# nav.net
KiCad netlist of a schematic drawn in EAGLE
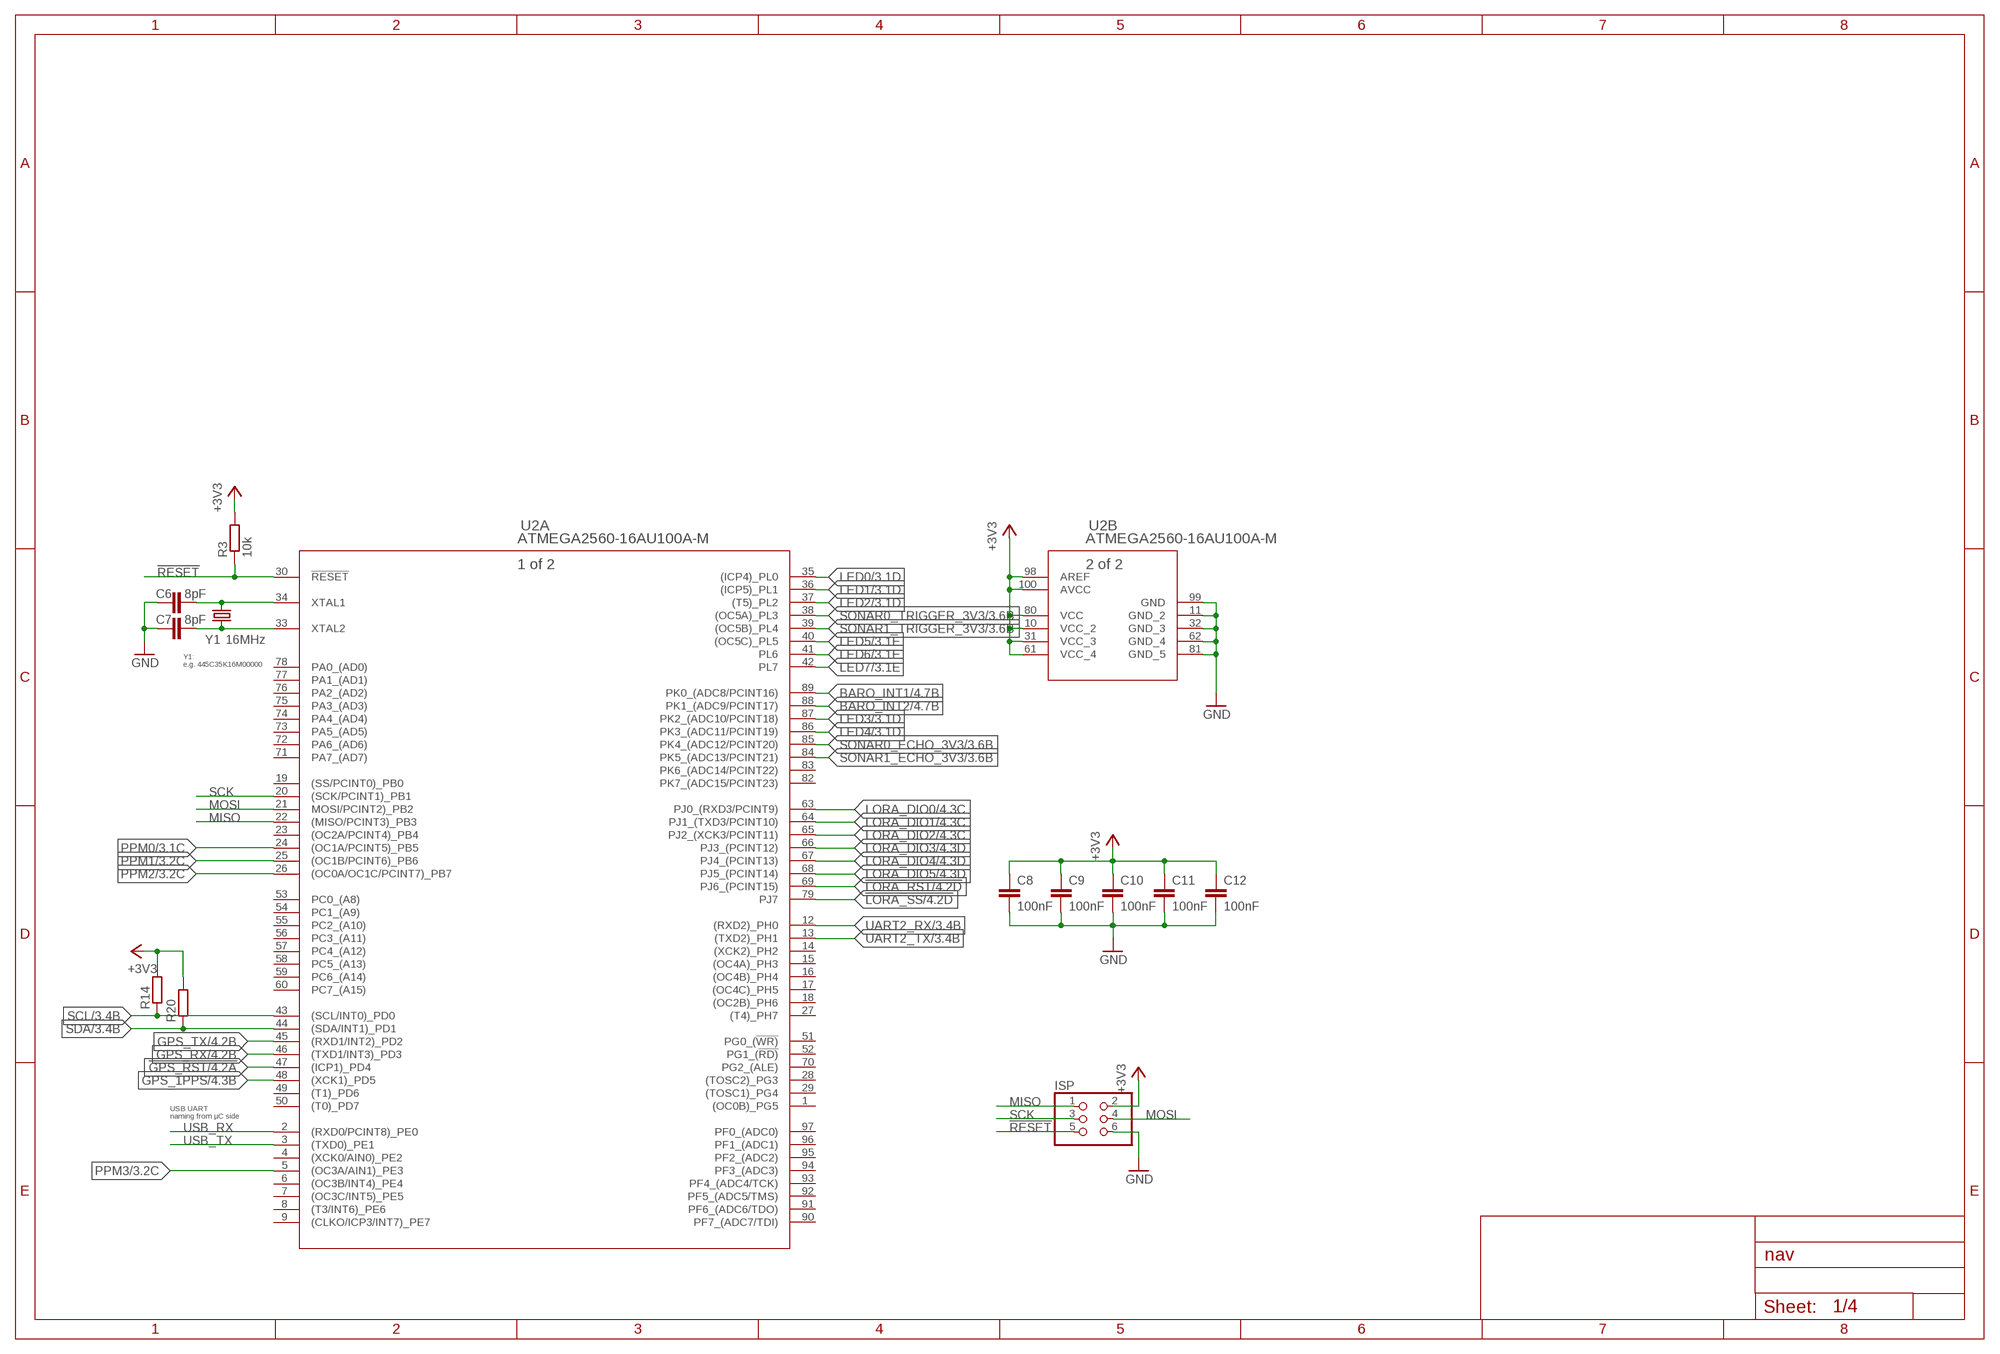
[diagram p0: schematic, sheet 1]
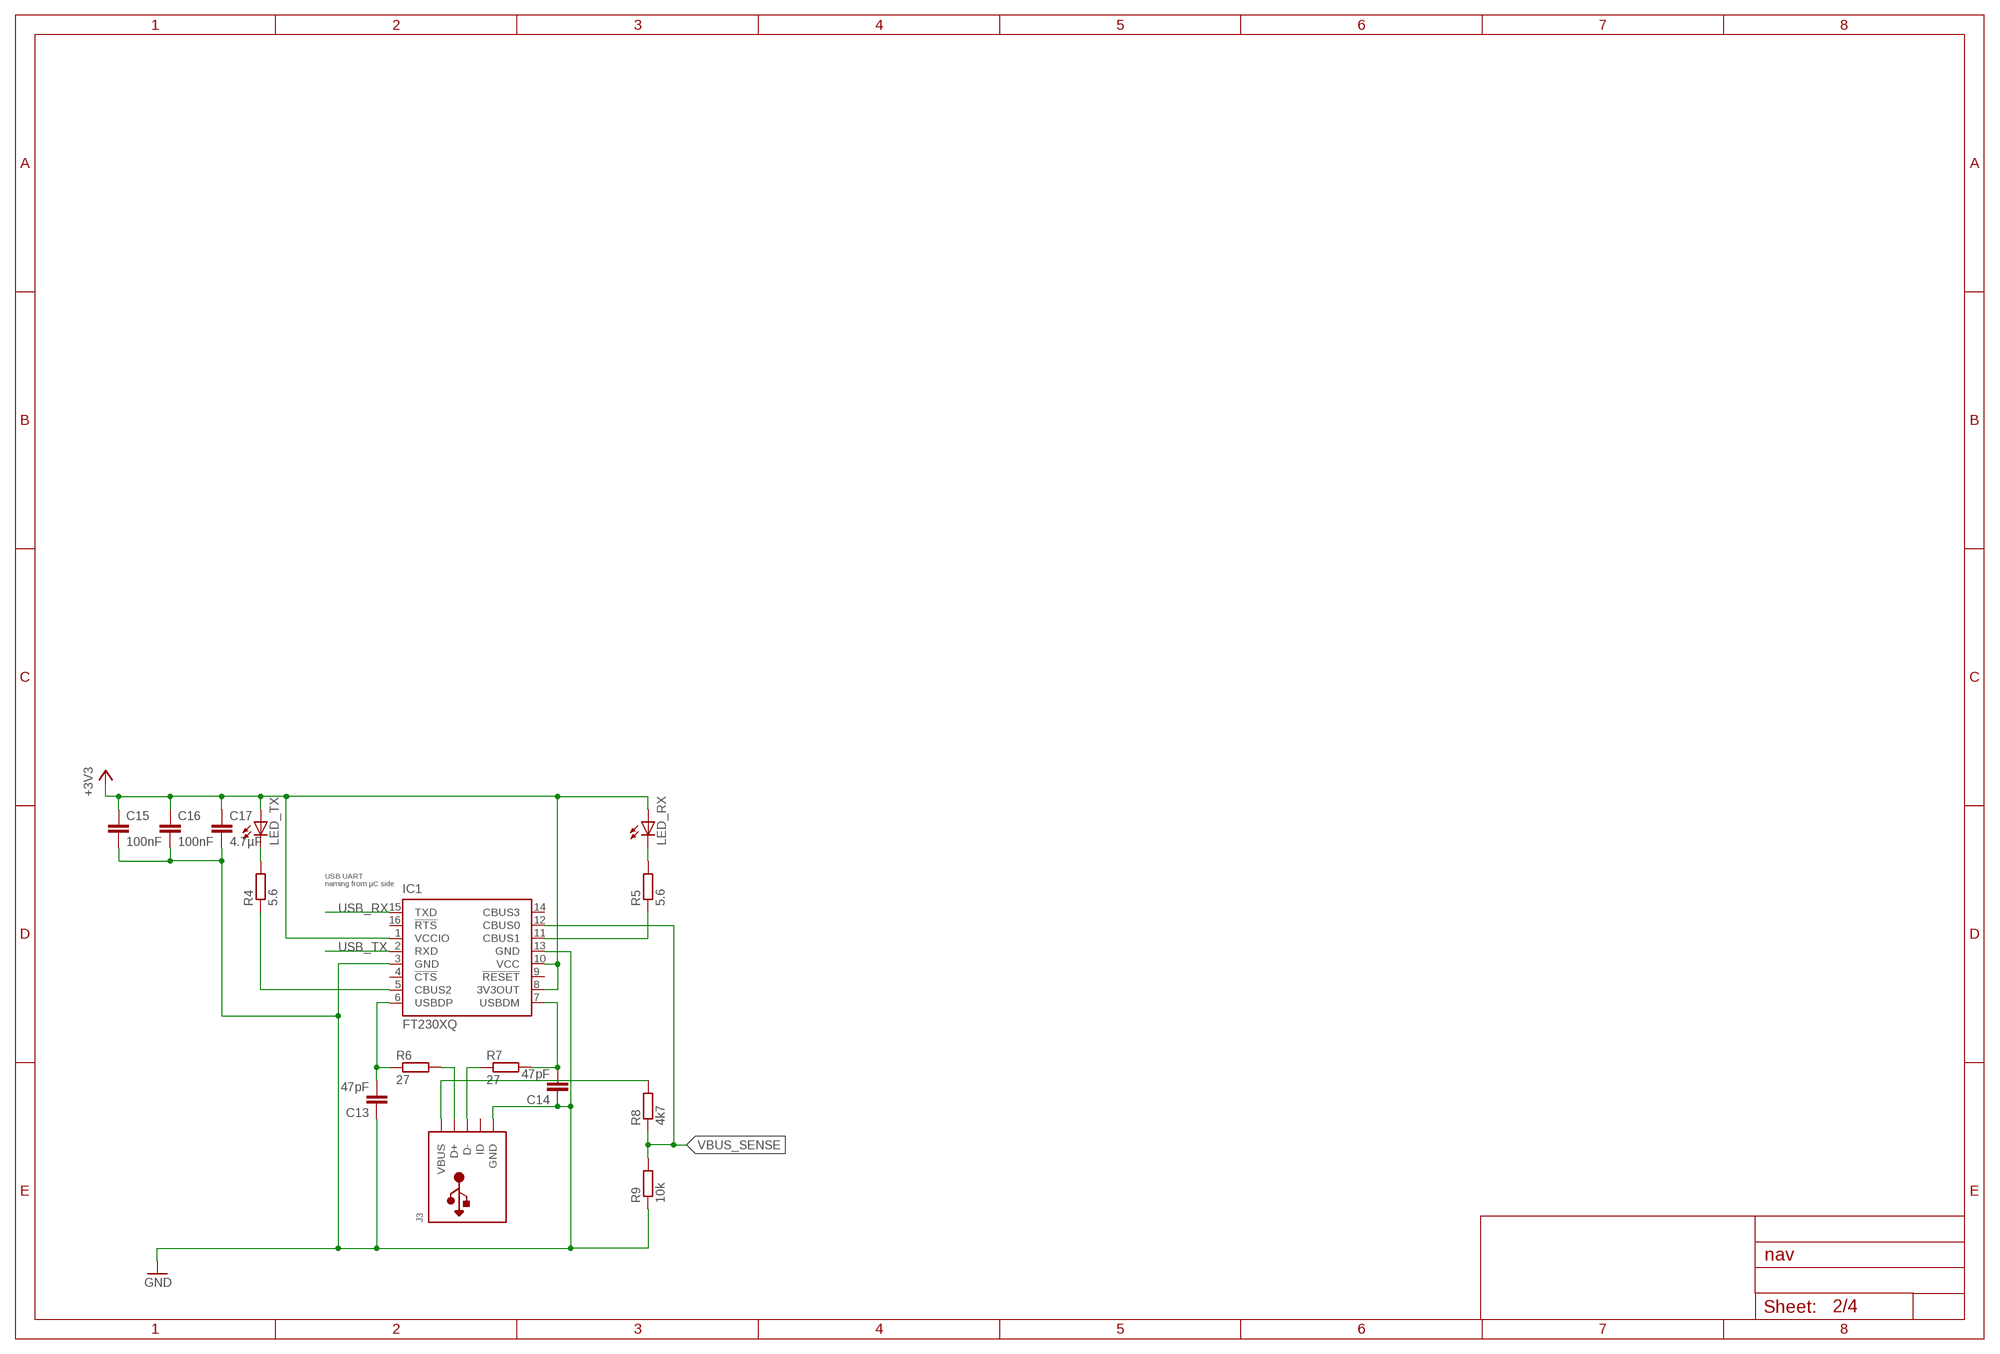
[diagram p1: schematic, sheet 2]
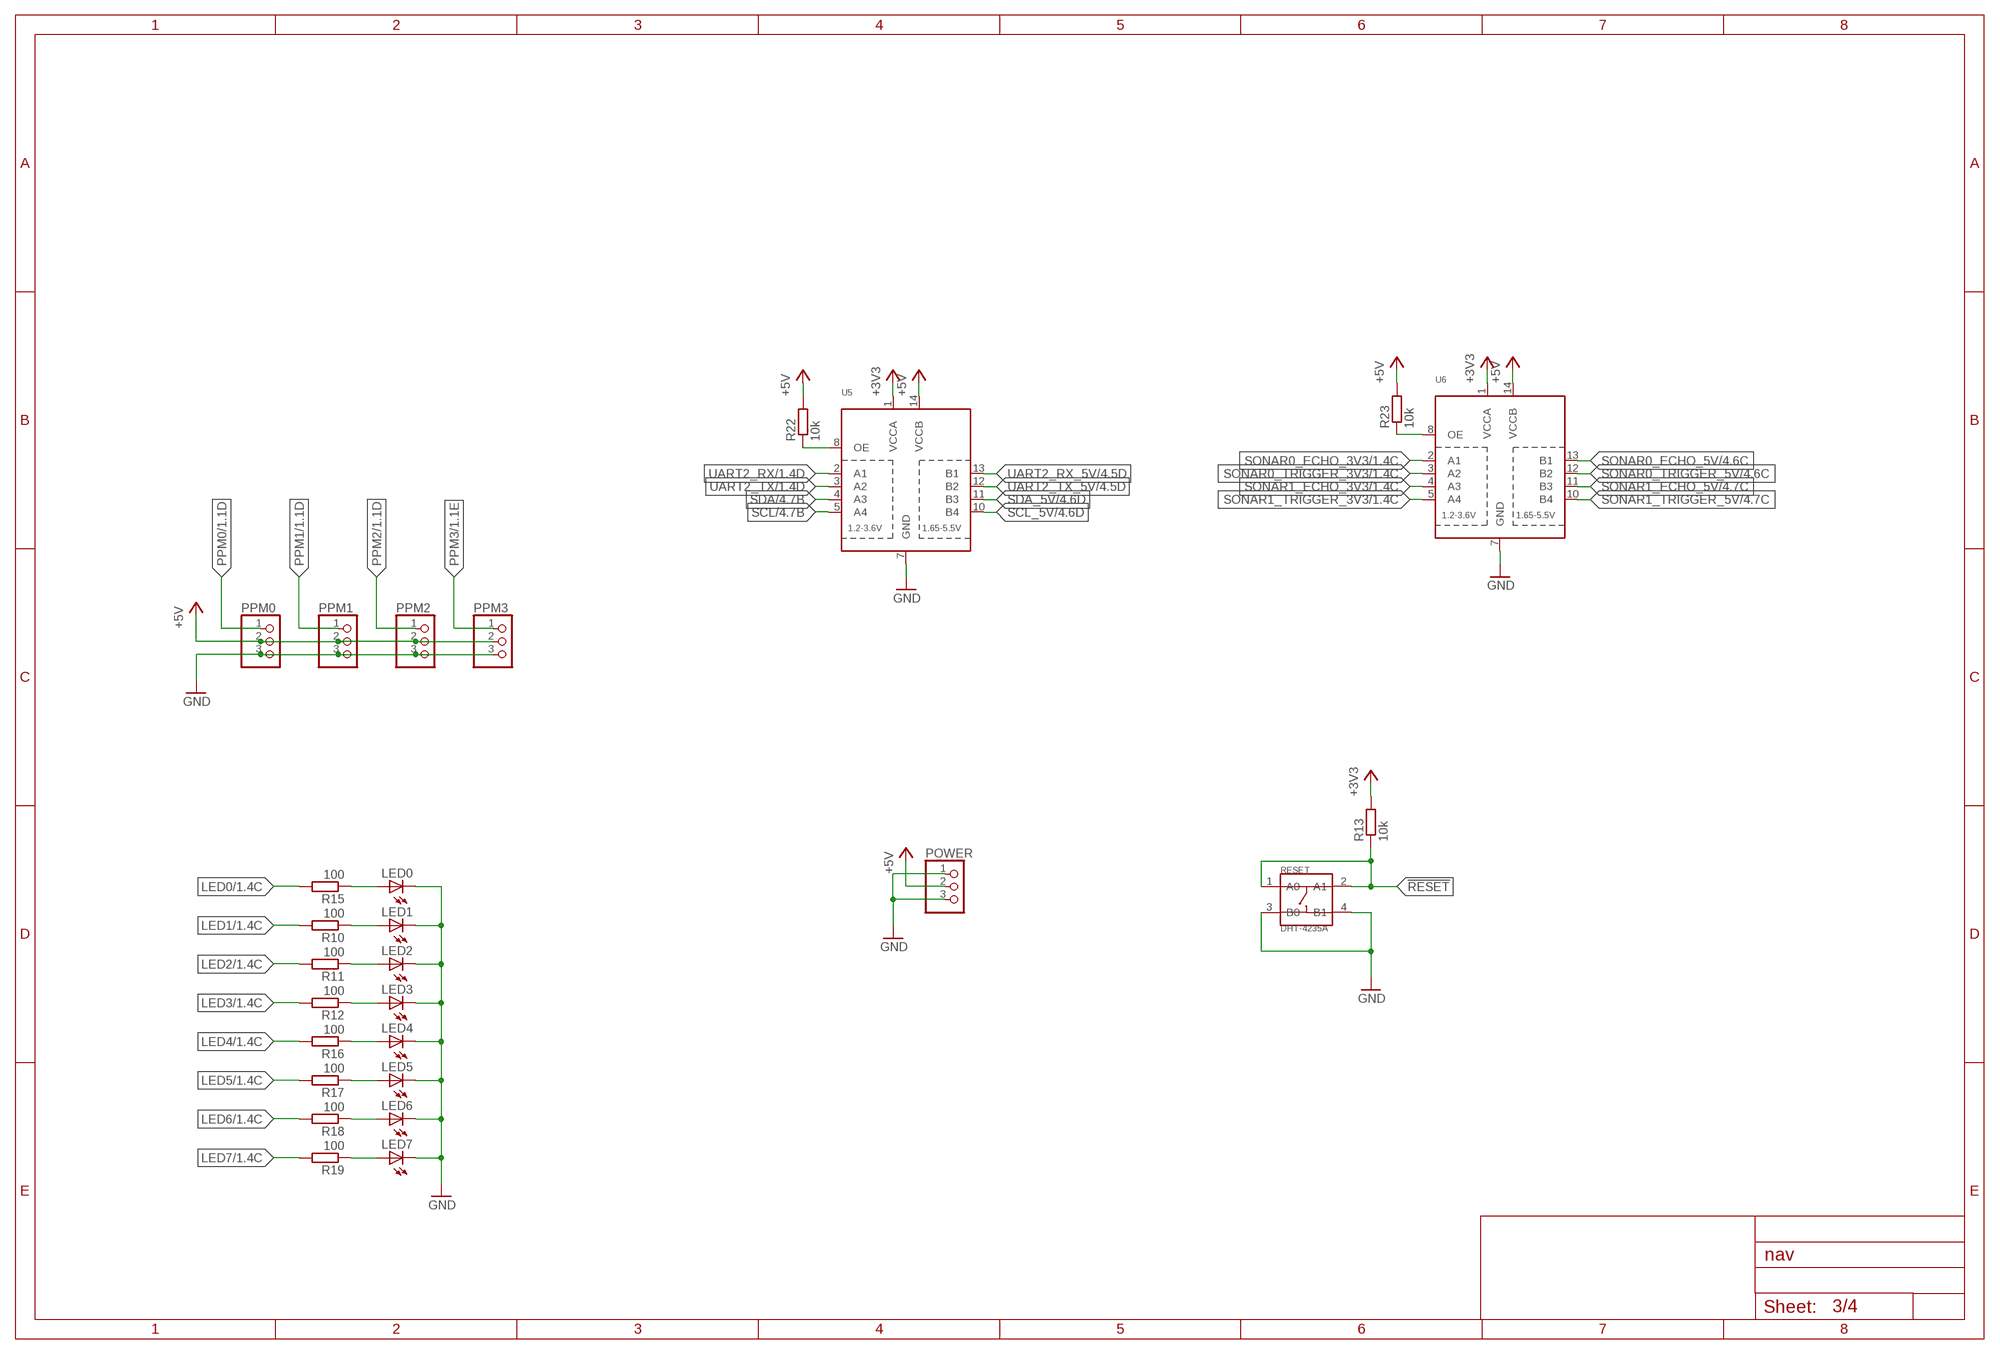
[diagram p2: schematic, sheet 3]
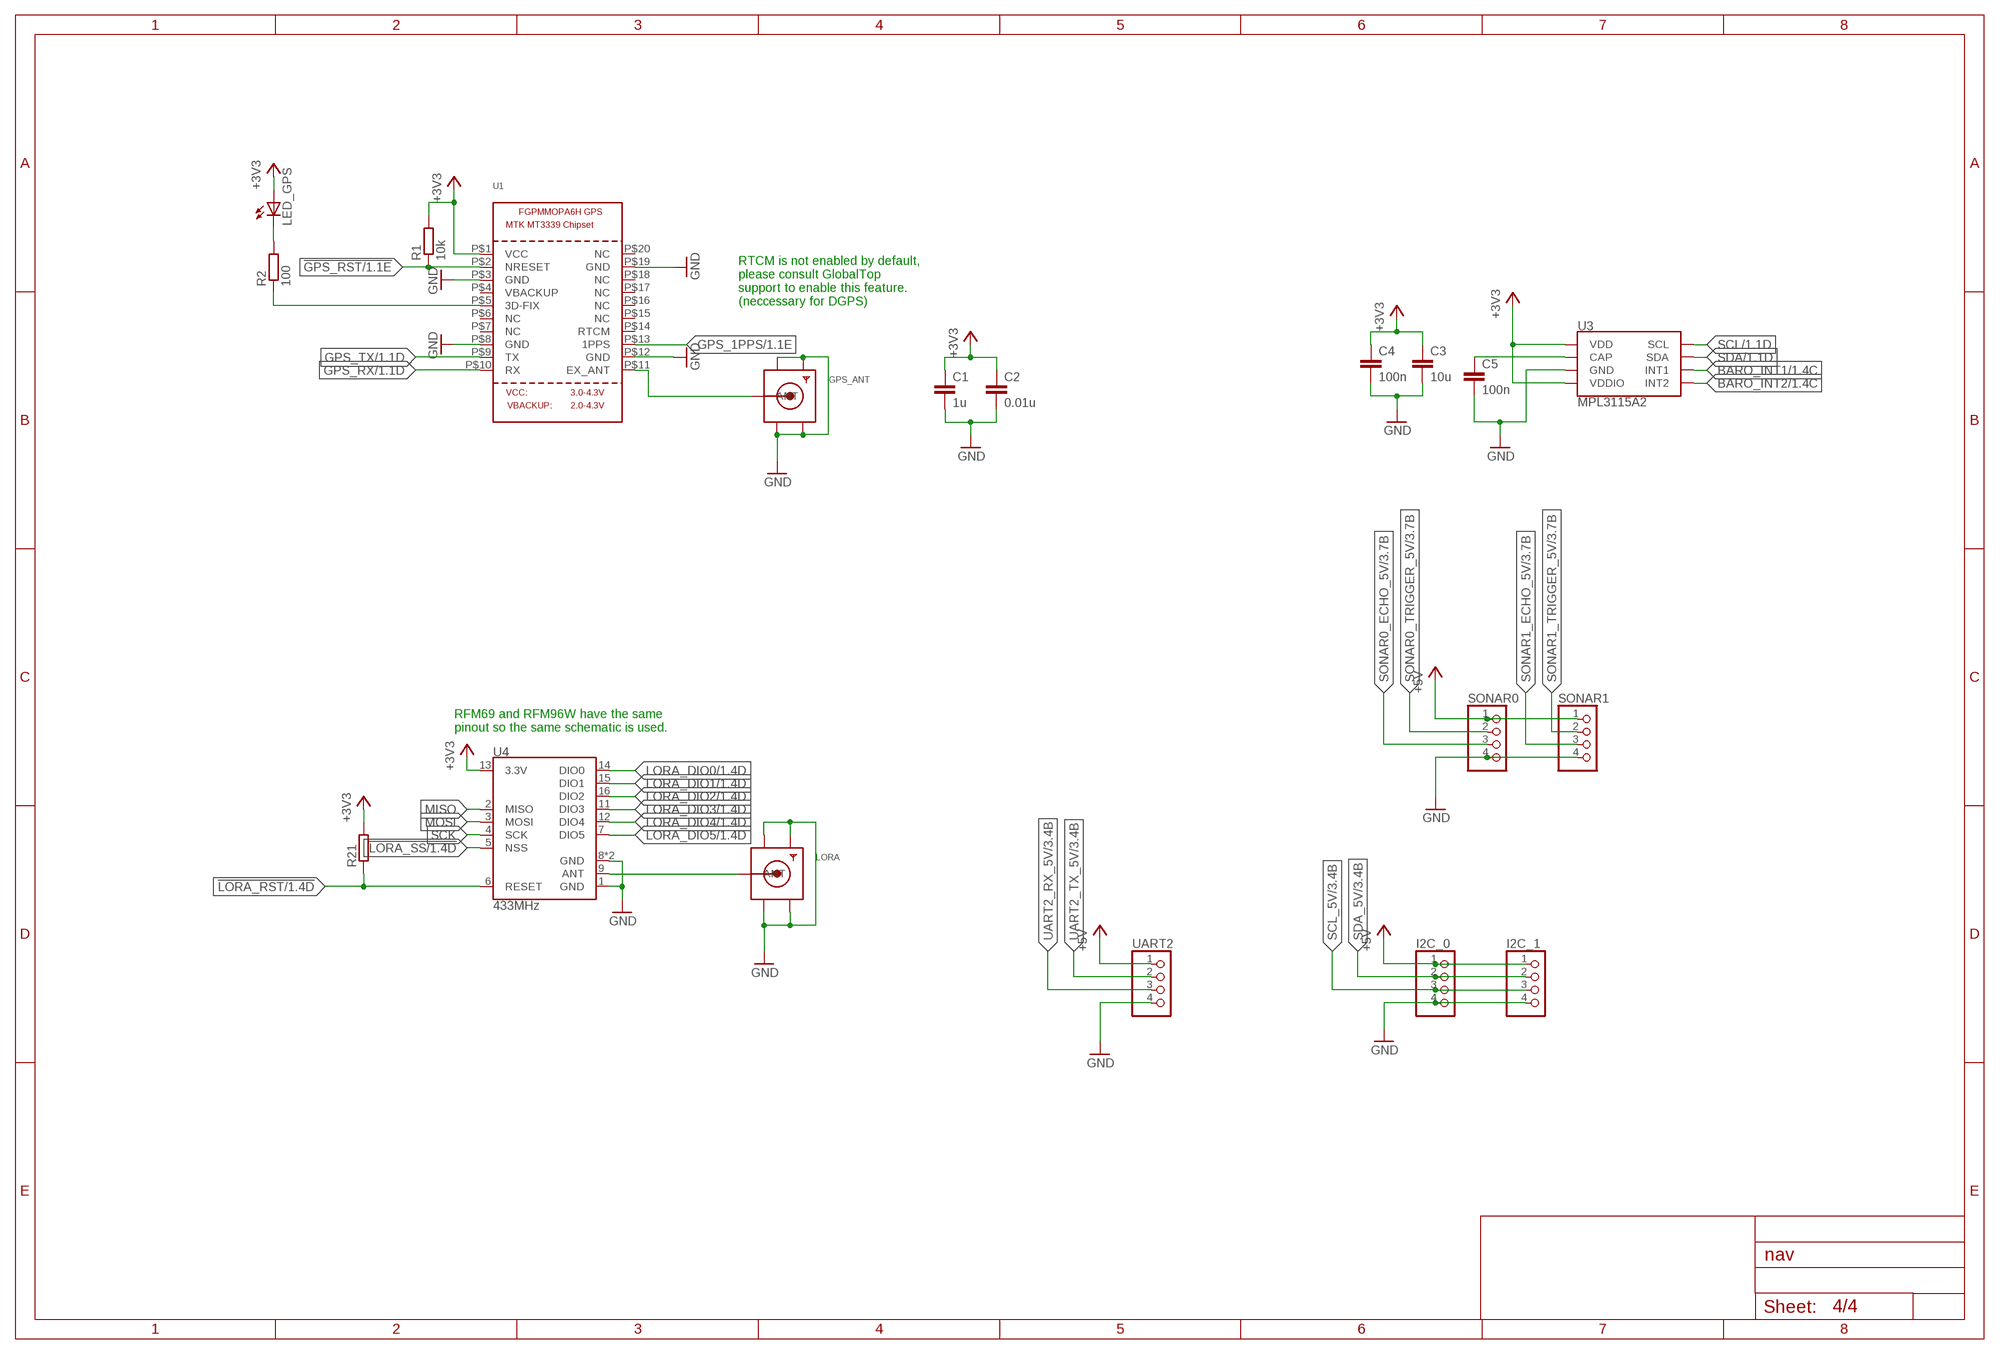
[diagram p3: schematic, sheet 4]

(export (version "E")
  (design (tool "Eeschema 10.0.6"))
  (components
    (comp (ref "LED0")
      (value "LEDCHIP-LED0603")
      (footprint "eagle-import:CHIP-LED0603")
      (libsource (lib "eagle-import") (part "LEDCHIP-LED0603"))
    )
    (comp (ref "LED1")
      (value "LEDCHIP-LED0603")
      (footprint "eagle-import:CHIP-LED0603")
      (libsource (lib "eagle-import") (part "LEDCHIP-LED0603"))
    )
    (comp (ref "LED2")
      (value "LEDCHIP-LED0603")
      (footprint "eagle-import:CHIP-LED0603")
      (libsource (lib "eagle-import") (part "LEDCHIP-LED0603"))
    )
    (comp (ref "LED3")
      (value "LEDCHIP-LED0603")
      (footprint "eagle-import:CHIP-LED0603")
      (libsource (lib "eagle-import") (part "LEDCHIP-LED0603"))
    )
    (comp (ref "LED4")
      (value "LEDCHIP-LED0603")
      (footprint "eagle-import:CHIP-LED0603")
      (libsource (lib "eagle-import") (part "LEDCHIP-LED0603"))
    )
    (comp (ref "LED5")
      (value "LEDCHIP-LED0603")
      (footprint "eagle-import:CHIP-LED0603")
      (libsource (lib "eagle-import") (part "LEDCHIP-LED0603"))
    )
    (comp (ref "LED6")
      (value "LEDCHIP-LED0603")
      (footprint "eagle-import:CHIP-LED0603")
      (libsource (lib "eagle-import") (part "LEDCHIP-LED0603"))
    )
    (comp (ref "LED7")
      (value "LEDCHIP-LED0603")
      (footprint "eagle-import:CHIP-LED0603")
      (libsource (lib "eagle-import") (part "LEDCHIP-LED0603"))
    )
    (comp (ref "POWER")
      (value "PINHD-1X3")
      (footprint "eagle-import:1X03")
      (libsource (lib "eagle-import") (part "PINHD-1X3"))
    )
    (comp (ref "PPM0")
      (value "PINHD-1X3")
      (footprint "eagle-import:1X03")
      (libsource (lib "eagle-import") (part "PINHD-1X3"))
    )
    (comp (ref "PPM1")
      (value "PINHD-1X3")
      (footprint "eagle-import:1X03")
      (libsource (lib "eagle-import") (part "PINHD-1X3"))
    )
    (comp (ref "PPM2")
      (value "PINHD-1X3")
      (footprint "eagle-import:1X03")
      (libsource (lib "eagle-import") (part "PINHD-1X3"))
    )
    (comp (ref "PPM3")
      (value "PINHD-1X3")
      (footprint "eagle-import:1X03")
      (libsource (lib "eagle-import") (part "PINHD-1X3"))
    )
    (comp (ref "R10")
      (value "100")
      (footprint "eagle-import:R0603")
      (libsource (lib "eagle-import") (part "R-EU_R0603"))
    )
    (comp (ref "R11")
      (value "100")
      (footprint "eagle-import:R0603")
      (libsource (lib "eagle-import") (part "R-EU_R0603"))
    )
    (comp (ref "R12")
      (value "100")
      (footprint "eagle-import:R0603")
      (libsource (lib "eagle-import") (part "R-EU_R0603"))
    )
    (comp (ref "R13")
      (value "10k")
      (footprint "eagle-import:R0603")
      (libsource (lib "eagle-import") (part "resistor_348_R-EU_R0603"))
    )
    (comp (ref "R15")
      (value "100")
      (footprint "eagle-import:R0603")
      (libsource (lib "eagle-import") (part "R-EU_R0603"))
    )
    (comp (ref "R16")
      (value "100")
      (footprint "eagle-import:R0603")
      (libsource (lib "eagle-import") (part "R-EU_R0603"))
    )
    (comp (ref "R17")
      (value "100")
      (footprint "eagle-import:R0603")
      (libsource (lib "eagle-import") (part "R-EU_R0603"))
    )
    (comp (ref "R18")
      (value "100")
      (footprint "eagle-import:R0603")
      (libsource (lib "eagle-import") (part "R-EU_R0603"))
    )
    (comp (ref "R19")
      (value "100")
      (footprint "eagle-import:R0603")
      (libsource (lib "eagle-import") (part "R-EU_R0603"))
    )
    (comp (ref "R22")
      (value "10k")
      (footprint "eagle-import:R0603")
      (libsource (lib "eagle-import") (part "resistor_348_R-EU_R0603"))
    )
    (comp (ref "R23")
      (value "10k")
      (footprint "eagle-import:R0603")
      (libsource (lib "eagle-import") (part "resistor_348_R-EU_R0603"))
    )
    (comp (ref "RESET")
      (value "DHT-4235A")
      (footprint "eagle-import:SW4-SMD-4.2X3.2X2.5MM")
      (libsource (lib "eagle-import") (part "SMD-BUTTON-TOP-DHT-4235A(4P-4.2X3.2MM)"))
    )
    (comp (ref "U5")
      (value "TXB0104PWR")
      (footprint "eagle-import:TSSOP14")
      (libsource (lib "eagle-import") (part "TXB0104PWR"))
    )
    (comp (ref "U6")
      (value "TXB0104PWR")
      (footprint "eagle-import:TSSOP14")
      (libsource (lib "eagle-import") (part "TXB0104PWR"))
    )
    (comp (ref "C6")
      (value "8pF")
      (footprint "eagle-import:C0603")
      (libsource (lib "eagle-import") (part "C-EUC0603"))
    )
    (comp (ref "C7")
      (value "8pF")
      (footprint "eagle-import:C0603")
      (libsource (lib "eagle-import") (part "C-EUC0603"))
    )
    (comp (ref "C8")
      (value "100nF")
      (footprint "eagle-import:C0603")
      (libsource (lib "eagle-import") (part "C-EUC0603"))
    )
    (comp (ref "C9")
      (value "100nF")
      (footprint "eagle-import:C0603")
      (libsource (lib "eagle-import") (part "C-EUC0603"))
    )
    (comp (ref "C10")
      (value "100nF")
      (footprint "eagle-import:C0603")
      (libsource (lib "eagle-import") (part "C-EUC0603"))
    )
    (comp (ref "C11")
      (value "100nF")
      (footprint "eagle-import:C0603")
      (libsource (lib "eagle-import") (part "C-EUC0603"))
    )
    (comp (ref "C12")
      (value "100nF")
      (footprint "eagle-import:C0603")
      (libsource (lib "eagle-import") (part "C-EUC0603"))
    )
    (comp (ref "ISP")
      (value "PINHD-2X3")
      (footprint "eagle-import:2X03")
      (libsource (lib "eagle-import") (part "PINHD-2X3"))
    )
    (comp (ref "R3")
      (value "10k")
      (footprint "eagle-import:R0603")
      (libsource (lib "eagle-import") (part "R-EU_R0603"))
    )
    (comp (ref "R14")
      (value "R-EU_R0603")
      (footprint "eagle-import:R0603")
      (libsource (lib "eagle-import") (part "resistor_348_R-EU_R0603"))
    )
    (comp (ref "R20")
      (value "R-EU_R0603")
      (footprint "eagle-import:R0603")
      (libsource (lib "eagle-import") (part "resistor_348_R-EU_R0603"))
    )
    (comp (ref "U2")
      (value "ATMEGA2560-16AU100A-M")
      (footprint "eagle-import:100A-M")
      (fields (field (name "MANUFACTURER_PART_NUMBER") "ATMEGA256016AU"))
      (libsource (lib "eagle-import") (part "ATMEGA2560-16AU100A-M"))
    )
    (comp (ref "Y1")
      (value "16MHz")
      (footprint "eagle-import:CRYSTAL-SMD-5X3.2-2PAD")
      (libsource (lib "eagle-import") (part "CRYSTALSMD-5X3.2-2PAD"))
    )
    (comp (ref "C13")
      (value "47pF")
      (footprint "eagle-import:C0603")
      (libsource (lib "eagle-import") (part "C-EUC0603"))
    )
    (comp (ref "C14")
      (value "47pF")
      (footprint "eagle-import:C0603")
      (libsource (lib "eagle-import") (part "C-EUC0603"))
    )
    (comp (ref "C15")
      (value "100nF")
      (footprint "eagle-import:C0603")
      (libsource (lib "eagle-import") (part "C-EUC0603"))
    )
    (comp (ref "C16")
      (value "100nF")
      (footprint "eagle-import:C0603")
      (libsource (lib "eagle-import") (part "C-EUC0603"))
    )
    (comp (ref "C17")
      (value "4.7µF")
      (footprint "eagle-import:C0603")
      (libsource (lib "eagle-import") (part "C-EUC0603"))
    )
    (comp (ref "IC1")
      (value "FT230XQ")
      (footprint "eagle-import:QFN16")
      (libsource (lib "eagle-import") (part "FT230XQ"))
    )
    (comp (ref "J3")
      (value "USBMINIB")
      (footprint "eagle-import:USB-MINIB")
      (libsource (lib "eagle-import") (part "USBMINIB"))
    )
    (comp (ref "LED_RX")
      (value "LEDCHIP-LED0603")
      (footprint "eagle-import:CHIP-LED0603")
      (libsource (lib "eagle-import") (part "LEDCHIP-LED0603"))
    )
    (comp (ref "LED_TX")
      (value "LEDCHIP-LED0603")
      (footprint "eagle-import:CHIP-LED0603")
      (libsource (lib "eagle-import") (part "LEDCHIP-LED0603"))
    )
    (comp (ref "R4")
      (value "5.6")
      (footprint "eagle-import:R0603")
      (libsource (lib "eagle-import") (part "R-EU_R0603"))
    )
    (comp (ref "R5")
      (value "5.6")
      (footprint "eagle-import:R0603")
      (libsource (lib "eagle-import") (part "R-EU_R0603"))
    )
    (comp (ref "R6")
      (value "27")
      (footprint "eagle-import:R0603")
      (libsource (lib "eagle-import") (part "R-EU_R0603"))
    )
    (comp (ref "R7")
      (value "27")
      (footprint "eagle-import:R0603")
      (libsource (lib "eagle-import") (part "R-EU_R0603"))
    )
    (comp (ref "R8")
      (value "4k7")
      (footprint "eagle-import:R0603")
      (libsource (lib "eagle-import") (part "R-EU_R0603"))
    )
    (comp (ref "R9")
      (value "10k")
      (footprint "eagle-import:R0603")
      (libsource (lib "eagle-import") (part "R-EU_R0603"))
    )
    (comp (ref "C1")
      (value "1u")
      (footprint "eagle-import:C0603")
      (libsource (lib "eagle-import") (part "resistor_348_C-EUC0603"))
    )
    (comp (ref "C2")
      (value "0.01u")
      (footprint "eagle-import:C0603")
      (libsource (lib "eagle-import") (part "resistor_348_C-EUC0603"))
    )
    (comp (ref "C3")
      (value "10u")
      (footprint "eagle-import:C0603")
      (libsource (lib "eagle-import") (part "resistor_348_C-EUC0603"))
    )
    (comp (ref "C4")
      (value "100n")
      (footprint "eagle-import:C0603")
      (libsource (lib "eagle-import") (part "resistor_348_C-EUC0603"))
    )
    (comp (ref "C5")
      (value "100n")
      (footprint "eagle-import:C0603")
      (libsource (lib "eagle-import") (part "resistor_348_C-EUC0603"))
    )
    (comp (ref "GPS_ANT")
      (value "SMACONNECTOR_EDGE")
      (footprint "eagle-import:SMA_EDGELAUNCH")
      (libsource (lib "eagle-import") (part "SMACONNECTOR_EDGE"))
    )
    (comp (ref "I2C_0")
      (value "PINHD-1X4")
      (footprint "eagle-import:1X04")
      (libsource (lib "eagle-import") (part "PINHD-1X4"))
    )
    (comp (ref "I2C_1")
      (value "PINHD-1X4")
      (footprint "eagle-import:1X04")
      (libsource (lib "eagle-import") (part "PINHD-1X4"))
    )
    (comp (ref "LED_GPS")
      (value "LEDCHIP-LED0603")
      (footprint "eagle-import:CHIP-LED0603")
      (libsource (lib "eagle-import") (part "LEDCHIP-LED0603"))
    )
    (comp (ref "LORA")
      (value "SMACONNECTOR_EDGE")
      (footprint "eagle-import:SMA_EDGELAUNCH")
      (libsource (lib "eagle-import") (part "SMACONNECTOR_EDGE"))
    )
    (comp (ref "R1")
      (value "10k")
      (footprint "eagle-import:R0603")
      (libsource (lib "eagle-import") (part "resistor_348_R-EU_R0603"))
    )
    (comp (ref "R2")
      (value "100")
      (footprint "eagle-import:R0603")
      (libsource (lib "eagle-import") (part "resistor_348_R-EU_R0603"))
    )
    (comp (ref "R21")
      (value "R-EU_R0603")
      (footprint "eagle-import:R0603")
      (libsource (lib "eagle-import") (part "resistor_348_R-EU_R0603"))
    )
    (comp (ref "SONAR0")
      (value "PINHD-1X4")
      (footprint "eagle-import:1X04")
      (libsource (lib "eagle-import") (part "PINHD-1X4"))
    )
    (comp (ref "SONAR1")
      (value "PINHD-1X4")
      (footprint "eagle-import:1X04")
      (libsource (lib "eagle-import") (part "PINHD-1X4"))
    )
    (comp (ref "U1")
      (value "GPS_FGPMMOPA6H")
      (footprint "eagle-import:FGPMMOPA6H")
      (libsource (lib "eagle-import") (part "GPS_FGPMMOPA6H"))
    )
    (comp (ref "U3")
      (value "MPL3115A2")
      (footprint "eagle-import:LGA-8-5X3")
      (libsource (lib "eagle-import") (part "MPL3115A2"))
    )
    (comp (ref "U4")
      (value "433MHz")
      (footprint "eagle-import:RFM69HCW-XXXS2")
      (libsource (lib "eagle-import") (part "RFM69HCW-433"))
    )
    (comp (ref "UART2")
      (value "PINHD-1X4")
      (footprint "eagle-import:1X04")
      (libsource (lib "eagle-import") (part "PINHD-1X4"))
    )
  )
  (nets
    (net (code "1") (name "+3V3") (class "Default")
      (node (ref "C1") (pin "1") (pinfunction "1_1") (pintype "passive"))
      (node (ref "C10") (pin "1") (pinfunction "1_1") (pintype "passive"))
      (node (ref "C11") (pin "1") (pinfunction "1_1") (pintype "passive"))
      (node (ref "C12") (pin "1") (pinfunction "1_1") (pintype "passive"))
      (node (ref "C15") (pin "1") (pinfunction "1_1") (pintype "passive"))
      (node (ref "C16") (pin "1") (pinfunction "1_1") (pintype "passive"))
      (node (ref "C17") (pin "1") (pinfunction "1_1") (pintype "passive"))
      (node (ref "C2") (pin "1") (pinfunction "1_1") (pintype "passive"))
      (node (ref "C3") (pin "1") (pinfunction "1_1") (pintype "passive"))
      (node (ref "C4") (pin "1") (pinfunction "1_1") (pintype "passive"))
      (node (ref "C8") (pin "1") (pinfunction "1_1") (pintype "passive"))
      (node (ref "C9") (pin "1") (pinfunction "1_1") (pintype "passive"))
      (node (ref "IC1") (pin "1") (pinfunction "VCCIO_1") (pintype "power_in"))
      (node (ref "IC1") (pin "10") (pinfunction "VCC_10") (pintype "power_in"))
      (node (ref "IC1") (pin "8") (pinfunction "3V3OUT_8") (pintype "output"))
      (node (ref "ISP") (pin "2") (pinfunction "2_2") (pintype "passive"))
      (node (ref "LED_GPS") (pin "A") (pinfunction "A_A") (pintype "passive"))
      (node (ref "LED_RX") (pin "A") (pinfunction "A_A") (pintype "passive"))
      (node (ref "LED_TX") (pin "A") (pinfunction "A_A") (pintype "passive"))
      (node (ref "R1") (pin "2") (pinfunction "2_2") (pintype "passive"))
      (node (ref "R13") (pin "2") (pinfunction "2_2") (pintype "passive"))
      (node (ref "R14") (pin "2") (pinfunction "2_2") (pintype "passive"))
      (node (ref "R20") (pin "2") (pinfunction "2_2") (pintype "passive"))
      (node (ref "R21") (pin "2") (pinfunction "2_2") (pintype "passive"))
      (node (ref "R3") (pin "2") (pinfunction "2_2") (pintype "passive"))
      (node (ref "U1") (pin "P$1") (pinfunction "VCC_P$1") (pintype "bidirectional"))
      (node (ref "U2") (pin "10") (pinfunction "VCC_2_10") (pintype "power_in"))
      (node (ref "U2") (pin "100") (pinfunction "AVCC_100") (pintype "power_in"))
      (node (ref "U2") (pin "31") (pinfunction "VCC_3_31") (pintype "power_in"))
      (node (ref "U2") (pin "61") (pinfunction "VCC_4_61") (pintype "power_in"))
      (node (ref "U2") (pin "80") (pinfunction "VCC_80") (pintype "power_in"))
      (node (ref "U2") (pin "98") (pinfunction "AREF_98") (pintype "power_in"))
      (node (ref "U3") (pin "1") (pinfunction "VDD_1") (pintype "power_in"))
      (node (ref "U3") (pin "4") (pinfunction "VDDIO_4") (pintype "power_in"))
      (node (ref "U4") (pin "13") (pinfunction "3.3V_13") (pintype "power_in"))
      (node (ref "U5") (pin "1") (pinfunction "VCCA_1") (pintype "bidirectional"))
      (node (ref "U6") (pin "1") (pinfunction "VCCA_1") (pintype "bidirectional"))
    )
    (net (code "2") (name "+5V") (class "Default")
      (node (ref "I2C_0") (pin "1") (pinfunction "1_1") (pintype "passive"))
      (node (ref "I2C_1") (pin "1") (pinfunction "1_1") (pintype "passive"))
      (node (ref "POWER") (pin "2") (pinfunction "2_2") (pintype "passive"))
      (node (ref "PPM0") (pin "2") (pinfunction "2_2") (pintype "passive"))
      (node (ref "PPM1") (pin "2") (pinfunction "2_2") (pintype "passive"))
      (node (ref "PPM2") (pin "2") (pinfunction "2_2") (pintype "passive"))
      (node (ref "PPM3") (pin "2") (pinfunction "2_2") (pintype "passive"))
      (node (ref "R22") (pin "2") (pinfunction "2_2") (pintype "passive"))
      (node (ref "R23") (pin "2") (pinfunction "2_2") (pintype "passive"))
      (node (ref "SONAR0") (pin "1") (pinfunction "1_1") (pintype "passive"))
      (node (ref "SONAR1") (pin "1") (pinfunction "1_1") (pintype "passive"))
      (node (ref "U5") (pin "14") (pinfunction "VCCB_14") (pintype "bidirectional"))
      (node (ref "U6") (pin "14") (pinfunction "VCCB_14") (pintype "bidirectional"))
      (node (ref "UART2") (pin "1") (pinfunction "1_1") (pintype "passive"))
    )
    (net (code "3") (name "BARO_INT1") (class "Default")
      (node (ref "U2") (pin "89") (pinfunction "PK0_(ADC8/PCINT16)_89") (pintype "bidirectional"))
      (node (ref "U3") (pin "6") (pinfunction "INT1_6") (pintype "output"))
    )
    (net (code "4") (name "BARO_INT2") (class "Default")
      (node (ref "U2") (pin "88") (pinfunction "PK1_(ADC9/PCINT17)_88") (pintype "bidirectional"))
      (node (ref "U3") (pin "5") (pinfunction "INT2_5") (pintype "output"))
    )
    (net (code "5") (name "GND") (class "Default")
      (node (ref "C1") (pin "2") (pinfunction "2_2") (pintype "passive"))
      (node (ref "C10") (pin "2") (pinfunction "2_2") (pintype "passive"))
      (node (ref "C11") (pin "2") (pinfunction "2_2") (pintype "passive"))
      (node (ref "C12") (pin "2") (pinfunction "2_2") (pintype "passive"))
      (node (ref "C13") (pin "1") (pinfunction "1_1") (pintype "passive"))
      (node (ref "C14") (pin "1") (pinfunction "1_1") (pintype "passive"))
      (node (ref "C15") (pin "2") (pinfunction "2_2") (pintype "passive"))
      (node (ref "C16") (pin "2") (pinfunction "2_2") (pintype "passive"))
      (node (ref "C17") (pin "2") (pinfunction "2_2") (pintype "passive"))
      (node (ref "C2") (pin "2") (pinfunction "2_2") (pintype "passive"))
      (node (ref "C3") (pin "2") (pinfunction "2_2") (pintype "passive"))
      (node (ref "C4") (pin "2") (pinfunction "2_2") (pintype "passive"))
      (node (ref "C5") (pin "2") (pinfunction "2_2") (pintype "passive"))
      (node (ref "C6") (pin "1") (pinfunction "1_1") (pintype "passive"))
      (node (ref "C7") (pin "1") (pinfunction "1_1") (pintype "passive"))
      (node (ref "C8") (pin "2") (pinfunction "2_2") (pintype "passive"))
      (node (ref "C9") (pin "2") (pinfunction "2_2") (pintype "passive"))
      (node (ref "GPS_ANT") (pin "GND@1") (pinfunction "GND4_GND@1") (pintype "power_in"))
      (node (ref "GPS_ANT") (pin "GND@2") (pinfunction "GND3_GND@2") (pintype "power_in"))
      (node (ref "GPS_ANT") (pin "GND@3") (pinfunction "GND2_GND@3") (pintype "power_in"))
      (node (ref "GPS_ANT") (pin "GND@4") (pinfunction "GND1_GND@4") (pintype "power_in"))
      (node (ref "I2C_0") (pin "4") (pinfunction "4_4") (pintype "passive"))
      (node (ref "I2C_1") (pin "4") (pinfunction "4_4") (pintype "passive"))
      (node (ref "IC1") (pin "13") (pinfunction "GND_13") (pintype "power_in"))
      (node (ref "IC1") (pin "3") (pinfunction "GND_3") (pintype "power_in"))
      (node (ref "ISP") (pin "6") (pinfunction "6_6") (pintype "passive"))
      (node (ref "J3") (pin "GND") (pinfunction "GND_GND") (pintype "power_in"))
      (node (ref "LED0") (pin "C") (pinfunction "C_C") (pintype "passive"))
      (node (ref "LED1") (pin "C") (pinfunction "C_C") (pintype "passive"))
      (node (ref "LED2") (pin "C") (pinfunction "C_C") (pintype "passive"))
      (node (ref "LED3") (pin "C") (pinfunction "C_C") (pintype "passive"))
      (node (ref "LED4") (pin "C") (pinfunction "C_C") (pintype "passive"))
      (node (ref "LED5") (pin "C") (pinfunction "C_C") (pintype "passive"))
      (node (ref "LED6") (pin "C") (pinfunction "C_C") (pintype "passive"))
      (node (ref "LED7") (pin "C") (pinfunction "C_C") (pintype "passive"))
      (node (ref "LORA") (pin "GND@1") (pinfunction "GND4_GND@1") (pintype "power_in"))
      (node (ref "LORA") (pin "GND@2") (pinfunction "GND3_GND@2") (pintype "power_in"))
      (node (ref "LORA") (pin "GND@3") (pinfunction "GND2_GND@3") (pintype "power_in"))
      (node (ref "LORA") (pin "GND@4") (pinfunction "GND1_GND@4") (pintype "power_in"))
      (node (ref "POWER") (pin "1") (pinfunction "1_1") (pintype "passive"))
      (node (ref "POWER") (pin "3") (pinfunction "3_3") (pintype "passive"))
      (node (ref "PPM0") (pin "3") (pinfunction "3_3") (pintype "passive"))
      (node (ref "PPM1") (pin "3") (pinfunction "3_3") (pintype "passive"))
      (node (ref "PPM2") (pin "3") (pinfunction "3_3") (pintype "passive"))
      (node (ref "PPM3") (pin "3") (pinfunction "3_3") (pintype "passive"))
      (node (ref "R9") (pin "1") (pinfunction "1_1") (pintype "passive"))
      (node (ref "RESET") (pin "3") (pinfunction "B0_3") (pintype "bidirectional"))
      (node (ref "RESET") (pin "4") (pinfunction "B1_4") (pintype "bidirectional"))
      (node (ref "SONAR0") (pin "4") (pinfunction "4_4") (pintype "passive"))
      (node (ref "SONAR1") (pin "4") (pinfunction "4_4") (pintype "passive"))
      (node (ref "U1") (pin "P$12") (pinfunction "GND_P$12") (pintype "bidirectional"))
      (node (ref "U1") (pin "P$19") (pinfunction "GND_P$19") (pintype "bidirectional"))
      (node (ref "U1") (pin "P$3") (pinfunction "GND_P$3") (pintype "bidirectional"))
      (node (ref "U1") (pin "P$8") (pinfunction "GND_P$8") (pintype "bidirectional"))
      (node (ref "U2") (pin "11") (pinfunction "GND_2_11") (pintype "power_in"))
      (node (ref "U2") (pin "32") (pinfunction "GND_3_32") (pintype "power_in"))
      (node (ref "U2") (pin "62") (pinfunction "GND_4_62") (pintype "power_in"))
      (node (ref "U2") (pin "81") (pinfunction "GND_5_81") (pintype "power_in"))
      (node (ref "U2") (pin "99") (pinfunction "GND_99") (pintype "passive"))
      (node (ref "U3") (pin "3") (pinfunction "GND_3") (pintype "power_in"))
      (node (ref "U4") (pin "1") (pinfunction "GND_1") (pintype "power_in"))
      (node (ref "U4") (pin "10") (pinfunction "GND_10") (pintype "power_in"))
      (node (ref "U4") (pin "8") (pinfunction "GND_8") (pintype "power_in"))
      (node (ref "U5") (pin "7") (pinfunction "GND_7") (pintype "bidirectional"))
      (node (ref "U6") (pin "7") (pinfunction "GND_7") (pintype "bidirectional"))
      (node (ref "UART2") (pin "4") (pinfunction "4_4") (pintype "passive"))
    )
    (net (code "6") (name "GPS_1PPS") (class "Default")
      (node (ref "U1") (pin "P$13") (pinfunction "1PPS_P$13") (pintype "bidirectional"))
      (node (ref "U2") (pin "48") (pinfunction "(XCK1)_PD5_48") (pintype "bidirectional"))
    )
    (net (code "7") (name "GPS_RX") (class "Default")
      (node (ref "U1") (pin "P$10") (pinfunction "RX_P$10") (pintype "bidirectional"))
      (node (ref "U2") (pin "46") (pinfunction "(TXD1/INT3)_PD3_46") (pintype "bidirectional"))
    )
    (net (code "8") (name "GPS_TX") (class "Default")
      (node (ref "U1") (pin "P$9") (pinfunction "TX_P$9") (pintype "bidirectional"))
      (node (ref "U2") (pin "45") (pinfunction "(RXD1/INT2)_PD2_45") (pintype "bidirectional"))
    )
    (net (code "9") (name "LED0") (class "Default")
      (node (ref "R15") (pin "2") (pinfunction "2_2") (pintype "passive"))
      (node (ref "U2") (pin "35") (pinfunction "(ICP4)_PL0_35") (pintype "bidirectional"))
    )
    (net (code "10") (name "LED1") (class "Default")
      (node (ref "R10") (pin "2") (pinfunction "2_2") (pintype "passive"))
      (node (ref "U2") (pin "36") (pinfunction "(ICP5)_PL1_36") (pintype "bidirectional"))
    )
    (net (code "11") (name "LED2") (class "Default")
      (node (ref "R11") (pin "2") (pinfunction "2_2") (pintype "passive"))
      (node (ref "U2") (pin "37") (pinfunction "(T5)_PL2_37") (pintype "bidirectional"))
    )
    (net (code "12") (name "LED3") (class "Default")
      (node (ref "R12") (pin "2") (pinfunction "2_2") (pintype "passive"))
      (node (ref "U2") (pin "87") (pinfunction "PK2_(ADC10/PCINT18)_87") (pintype "bidirectional"))
    )
    (net (code "13") (name "LED4") (class "Default")
      (node (ref "R16") (pin "2") (pinfunction "2_2") (pintype "passive"))
      (node (ref "U2") (pin "86") (pinfunction "PK3_(ADC11/PCINT19)_86") (pintype "bidirectional"))
    )
    (net (code "14") (name "LED5") (class "Default")
      (node (ref "R17") (pin "2") (pinfunction "2_2") (pintype "passive"))
      (node (ref "U2") (pin "40") (pinfunction "(OC5C)_PL5_40") (pintype "bidirectional"))
    )
    (net (code "15") (name "LED6") (class "Default")
      (node (ref "R18") (pin "2") (pinfunction "2_2") (pintype "passive"))
      (node (ref "U2") (pin "41") (pinfunction "PL6_41") (pintype "bidirectional"))
    )
    (net (code "16") (name "LED7") (class "Default")
      (node (ref "R19") (pin "2") (pinfunction "2_2") (pintype "passive"))
      (node (ref "U2") (pin "42") (pinfunction "PL7_42") (pintype "bidirectional"))
    )
    (net (code "17") (name "LORA_DIO0") (class "Default")
      (node (ref "U2") (pin "63") (pinfunction "PJ0_(RXD3/PCINT9)_63") (pintype "bidirectional"))
      (node (ref "U4") (pin "14") (pinfunction "DIO0_14") (pintype "bidirectional"))
    )
    (net (code "18") (name "LORA_DIO1") (class "Default")
      (node (ref "U2") (pin "64") (pinfunction "PJ1_(TXD3/PCINT10)_64") (pintype "bidirectional"))
      (node (ref "U4") (pin "15") (pinfunction "DIO1_15") (pintype "bidirectional"))
    )
    (net (code "19") (name "LORA_DIO2") (class "Default")
      (node (ref "U2") (pin "65") (pinfunction "PJ2_(XCK3/PCINT11)_65") (pintype "bidirectional"))
      (node (ref "U4") (pin "16") (pinfunction "DIO2_16") (pintype "bidirectional"))
    )
    (net (code "20") (name "LORA_DIO3") (class "Default")
      (node (ref "U2") (pin "66") (pinfunction "PJ3_(PCINT12)_66") (pintype "bidirectional"))
      (node (ref "U4") (pin "11") (pinfunction "DIO3_11") (pintype "bidirectional"))
    )
    (net (code "21") (name "LORA_DIO4") (class "Default")
      (node (ref "U2") (pin "67") (pinfunction "PJ4_(PCINT13)_67") (pintype "bidirectional"))
      (node (ref "U4") (pin "12") (pinfunction "DIO4_12") (pintype "bidirectional"))
    )
    (net (code "22") (name "LORA_DIO5") (class "Default")
      (node (ref "U2") (pin "68") (pinfunction "PJ5_(PCINT14)_68") (pintype "bidirectional"))
      (node (ref "U4") (pin "7") (pinfunction "DIO5_7") (pintype "bidirectional"))
    )
    (net (code "23") (name "MISO") (class "Default")
      (node (ref "ISP") (pin "1") (pinfunction "1_1") (pintype "passive"))
      (node (ref "U2") (pin "22") (pinfunction "(MISO/PCINT3)_PB3_22") (pintype "bidirectional"))
      (node (ref "U4") (pin "2") (pinfunction "MISO_2") (pintype "bidirectional"))
    )
    (net (code "24") (name "MOSI") (class "Default")
      (node (ref "ISP") (pin "4") (pinfunction "4_4") (pintype "passive"))
      (node (ref "U2") (pin "21") (pinfunction "MOSI/PCINT2)_PB2_21") (pintype "bidirectional"))
      (node (ref "U4") (pin "3") (pinfunction "MOSI_3") (pintype "input"))
    )
    (net (code "25") (name "Net-(GPS_ANT-ANT)") (class "Default")
      (node (ref "GPS_ANT") (pin "P") (pinfunction "ANT_P") (pintype "bidirectional"))
      (node (ref "U1") (pin "P$11") (pinfunction "EX_ANT_P$11") (pintype "bidirectional"))
    )
    (net (code "26") (name "Net-(IC1-CBUS1)") (class "Default")
      (node (ref "IC1") (pin "11") (pinfunction "CBUS1_11") (pintype "bidirectional"))
      (node (ref "R5") (pin "1") (pinfunction "1_1") (pintype "passive"))
    )
    (net (code "27") (name "Net-(IC1-CBUS2)") (class "Default")
      (node (ref "IC1") (pin "5") (pinfunction "CBUS2_5") (pintype "bidirectional"))
      (node (ref "R4") (pin "1") (pinfunction "1_1") (pintype "passive"))
    )
    (net (code "28") (name "Net-(IC1-USBDM)") (class "Default")
      (node (ref "C14") (pin "2") (pinfunction "2_2") (pintype "passive"))
      (node (ref "IC1") (pin "7") (pinfunction "USBDM_7") (pintype "input"))
      (node (ref "R7") (pin "2") (pinfunction "2_2") (pintype "passive"))
    )
    (net (code "29") (name "Net-(IC1-USBDP)") (class "Default")
      (node (ref "C13") (pin "2") (pinfunction "2_2") (pintype "passive"))
      (node (ref "IC1") (pin "6") (pinfunction "USBDP_6") (pintype "input"))
      (node (ref "R6") (pin "1") (pinfunction "1_1") (pintype "passive"))
    )
    (net (code "30") (name "Net-(J3-PadD+)") (class "Default")
      (node (ref "J3") (pin "D+") (pinfunction "D+_D+") (pintype "bidirectional"))
      (node (ref "R6") (pin "2") (pinfunction "2_2") (pintype "passive"))
    )
    (net (code "31") (name "Net-(J3-PadD-)") (class "Default")
      (node (ref "J3") (pin "D-") (pinfunction "D-_D-") (pintype "bidirectional"))
      (node (ref "R7") (pin "1") (pinfunction "1_1") (pintype "passive"))
    )
    (net (code "32") (name "Net-(J3-PadVBUS)") (class "Default")
      (node (ref "J3") (pin "VBUS") (pinfunction "VBUS_VBUS") (pintype "power_in"))
      (node (ref "R8") (pin "2") (pinfunction "2_2") (pintype "passive"))
    )
    (net (code "33") (name "Net-(LED0-PadA)") (class "Default")
      (node (ref "LED0") (pin "A") (pinfunction "A_A") (pintype "passive"))
      (node (ref "R15") (pin "1") (pinfunction "1_1") (pintype "passive"))
    )
    (net (code "34") (name "Net-(LED1-PadA)") (class "Default")
      (node (ref "LED1") (pin "A") (pinfunction "A_A") (pintype "passive"))
      (node (ref "R10") (pin "1") (pinfunction "1_1") (pintype "passive"))
    )
    (net (code "35") (name "Net-(LED2-PadA)") (class "Default")
      (node (ref "LED2") (pin "A") (pinfunction "A_A") (pintype "passive"))
      (node (ref "R11") (pin "1") (pinfunction "1_1") (pintype "passive"))
    )
    (net (code "36") (name "Net-(LED3-PadA)") (class "Default")
      (node (ref "LED3") (pin "A") (pinfunction "A_A") (pintype "passive"))
      (node (ref "R12") (pin "1") (pinfunction "1_1") (pintype "passive"))
    )
    (net (code "37") (name "Net-(LED4-PadA)") (class "Default")
      (node (ref "LED4") (pin "A") (pinfunction "A_A") (pintype "passive"))
      (node (ref "R16") (pin "1") (pinfunction "1_1") (pintype "passive"))
    )
    (net (code "38") (name "Net-(LED5-PadA)") (class "Default")
      (node (ref "LED5") (pin "A") (pinfunction "A_A") (pintype "passive"))
      (node (ref "R17") (pin "1") (pinfunction "1_1") (pintype "passive"))
    )
    (net (code "39") (name "Net-(LED6-PadA)") (class "Default")
      (node (ref "LED6") (pin "A") (pinfunction "A_A") (pintype "passive"))
      (node (ref "R18") (pin "1") (pinfunction "1_1") (pintype "passive"))
    )
    (net (code "40") (name "Net-(LED7-PadA)") (class "Default")
      (node (ref "LED7") (pin "A") (pinfunction "A_A") (pintype "passive"))
      (node (ref "R19") (pin "1") (pinfunction "1_1") (pintype "passive"))
    )
    (net (code "41") (name "Net-(LED_GPS-PadC)") (class "Default")
      (node (ref "LED_GPS") (pin "C") (pinfunction "C_C") (pintype "passive"))
      (node (ref "R2") (pin "2") (pinfunction "2_2") (pintype "passive"))
    )
    (net (code "42") (name "Net-(LED_RX-PadC)") (class "Default")
      (node (ref "LED_RX") (pin "C") (pinfunction "C_C") (pintype "passive"))
      (node (ref "R5") (pin "2") (pinfunction "2_2") (pintype "passive"))
    )
    (net (code "43") (name "Net-(LED_TX-PadC)") (class "Default")
      (node (ref "LED_TX") (pin "C") (pinfunction "C_C") (pintype "passive"))
      (node (ref "R4") (pin "2") (pinfunction "2_2") (pintype "passive"))
    )
    (net (code "44") (name "Net-(LORA-ANT)") (class "Default")
      (node (ref "LORA") (pin "P") (pinfunction "ANT_P") (pintype "bidirectional"))
      (node (ref "U4") (pin "9") (pinfunction "ANT_9") (pintype "passive"))
    )
    (net (code "45") (name "Net-(U1-3D-FIX)") (class "Default")
      (node (ref "R2") (pin "1") (pinfunction "1_1") (pintype "passive"))
      (node (ref "U1") (pin "P$5") (pinfunction "3D-FIX_P$5") (pintype "bidirectional"))
    )
    (net (code "46") (name "Net-(U2A-XTAL1)") (class "Default")
      (node (ref "C6") (pin "2") (pinfunction "2_2") (pintype "passive"))
      (node (ref "U2") (pin "34") (pinfunction "XTAL1_34") (pintype "input"))
      (node (ref "Y1") (pin "P$2") (pinfunction "2_P$2") (pintype "passive"))
    )
    (net (code "47") (name "Net-(U2A-XTAL2)") (class "Default")
      (node (ref "C7") (pin "2") (pinfunction "2_2") (pintype "passive"))
      (node (ref "U2") (pin "33") (pinfunction "XTAL2_33") (pintype "output"))
      (node (ref "Y1") (pin "P$1") (pinfunction "1_P$1") (pintype "passive"))
    )
    (net (code "48") (name "Net-(U3-CAP)") (class "Default")
      (node (ref "C5") (pin "1") (pinfunction "1_1") (pintype "passive"))
      (node (ref "U3") (pin "2") (pinfunction "CAP_2") (pintype "power_in"))
    )
    (net (code "49") (name "Net-(U5-OE)") (class "Default")
      (node (ref "R22") (pin "1") (pinfunction "1_1") (pintype "passive"))
      (node (ref "U5") (pin "8") (pinfunction "OE_8") (pintype "bidirectional"))
    )
    (net (code "50") (name "Net-(U6-OE)") (class "Default")
      (node (ref "R23") (pin "1") (pinfunction "1_1") (pintype "passive"))
      (node (ref "U6") (pin "8") (pinfunction "OE_8") (pintype "bidirectional"))
    )
    (net (code "51") (name "PPM0") (class "Default")
      (node (ref "PPM0") (pin "1") (pinfunction "1_1") (pintype "passive"))
      (node (ref "U2") (pin "24") (pinfunction "(OC1A/PCINT5)_PB5_24") (pintype "bidirectional"))
    )
    (net (code "52") (name "PPM1") (class "Default")
      (node (ref "PPM1") (pin "1") (pinfunction "1_1") (pintype "passive"))
      (node (ref "U2") (pin "25") (pinfunction "(OC1B/PCINT6)_PB6_25") (pintype "bidirectional"))
    )
    (net (code "53") (name "PPM2") (class "Default")
      (node (ref "PPM2") (pin "1") (pinfunction "1_1") (pintype "passive"))
      (node (ref "U2") (pin "26") (pinfunction "(OC0A/OC1C/PCINT7)_PB7_26") (pintype "bidirectional"))
    )
    (net (code "54") (name "PPM3") (class "Default")
      (node (ref "PPM3") (pin "1") (pinfunction "1_1") (pintype "passive"))
      (node (ref "U2") (pin "5") (pinfunction "(OC3A/AIN1)_PE3_5") (pintype "bidirectional"))
    )
    (net (code "55") (name "SCK") (class "Default")
      (node (ref "ISP") (pin "3") (pinfunction "3_3") (pintype "passive"))
      (node (ref "U2") (pin "20") (pinfunction "(SCK/PCINT1)_PB1_20") (pintype "bidirectional"))
      (node (ref "U4") (pin "4") (pinfunction "SCK_4") (pintype "input"))
    )
    (net (code "56") (name "SCL") (class "Default")
      (node (ref "R14") (pin "1") (pinfunction "1_1") (pintype "passive"))
      (node (ref "U2") (pin "43") (pinfunction "(SCL/INT0)_PD0_43") (pintype "bidirectional"))
      (node (ref "U3") (pin "8") (pinfunction "SCL_8") (pintype "bidirectional"))
      (node (ref "U5") (pin "5") (pinfunction "A4_5") (pintype "bidirectional"))
    )
    (net (code "57") (name "SCL_5V") (class "Default")
      (node (ref "I2C_0") (pin "3") (pinfunction "3_3") (pintype "passive"))
      (node (ref "I2C_1") (pin "3") (pinfunction "3_3") (pintype "passive"))
      (node (ref "U5") (pin "10") (pinfunction "B4_10") (pintype "bidirectional"))
    )
    (net (code "58") (name "SDA") (class "Default")
      (node (ref "R20") (pin "1") (pinfunction "1_1") (pintype "passive"))
      (node (ref "U2") (pin "44") (pinfunction "(SDA/INT1)_PD1_44") (pintype "bidirectional"))
      (node (ref "U3") (pin "7") (pinfunction "SDA_7") (pintype "bidirectional"))
      (node (ref "U5") (pin "4") (pinfunction "A3_4") (pintype "bidirectional"))
    )
    (net (code "59") (name "SDA_5V") (class "Default")
      (node (ref "I2C_0") (pin "2") (pinfunction "2_2") (pintype "passive"))
      (node (ref "I2C_1") (pin "2") (pinfunction "2_2") (pintype "passive"))
      (node (ref "U5") (pin "11") (pinfunction "B3_11") (pintype "bidirectional"))
    )
    (net (code "60") (name "SONAR0_ECHO_3V3") (class "Default")
      (node (ref "U2") (pin "85") (pinfunction "PK4_(ADC12/PCINT20)_85") (pintype "bidirectional"))
      (node (ref "U6") (pin "2") (pinfunction "A1_2") (pintype "bidirectional"))
    )
    (net (code "61") (name "SONAR0_ECHO_5V") (class "Default")
      (node (ref "SONAR0") (pin "3") (pinfunction "3_3") (pintype "passive"))
      (node (ref "U6") (pin "13") (pinfunction "B1_13") (pintype "bidirectional"))
    )
    (net (code "62") (name "SONAR0_TRIGGER_3V3") (class "Default")
      (node (ref "U2") (pin "38") (pinfunction "(OC5A)_PL3_38") (pintype "bidirectional"))
      (node (ref "U6") (pin "3") (pinfunction "A2_3") (pintype "bidirectional"))
    )
    (net (code "63") (name "SONAR0_TRIGGER_5V") (class "Default")
      (node (ref "SONAR0") (pin "2") (pinfunction "2_2") (pintype "passive"))
      (node (ref "U6") (pin "12") (pinfunction "B2_12") (pintype "bidirectional"))
    )
    (net (code "64") (name "SONAR1_ECHO_3V3") (class "Default")
      (node (ref "U2") (pin "84") (pinfunction "PK5_(ADC13/PCINT21)_84") (pintype "bidirectional"))
      (node (ref "U6") (pin "4") (pinfunction "A3_4") (pintype "bidirectional"))
    )
    (net (code "65") (name "SONAR1_ECHO_5V") (class "Default")
      (node (ref "SONAR1") (pin "3") (pinfunction "3_3") (pintype "passive"))
      (node (ref "U6") (pin "11") (pinfunction "B3_11") (pintype "bidirectional"))
    )
    (net (code "66") (name "SONAR1_TRIGGER_3V3") (class "Default")
      (node (ref "U2") (pin "39") (pinfunction "(OC5B)_PL4_39") (pintype "bidirectional"))
      (node (ref "U6") (pin "5") (pinfunction "A4_5") (pintype "bidirectional"))
    )
    (net (code "67") (name "SONAR1_TRIGGER_5V") (class "Default")
      (node (ref "SONAR1") (pin "2") (pinfunction "2_2") (pintype "passive"))
      (node (ref "U6") (pin "10") (pinfunction "B4_10") (pintype "bidirectional"))
    )
    (net (code "68") (name "UART2_RX") (class "Default")
      (node (ref "U2") (pin "12") (pinfunction "(RXD2)_PH0_12") (pintype "bidirectional"))
      (node (ref "U5") (pin "2") (pinfunction "A1_2") (pintype "bidirectional"))
    )
    (net (code "69") (name "UART2_RX_5V") (class "Default")
      (node (ref "U5") (pin "13") (pinfunction "B1_13") (pintype "bidirectional"))
      (node (ref "UART2") (pin "3") (pinfunction "3_3") (pintype "passive"))
    )
    (net (code "70") (name "UART2_TX") (class "Default")
      (node (ref "U2") (pin "13") (pinfunction "(TXD2)_PH1_13") (pintype "bidirectional"))
      (node (ref "U5") (pin "3") (pinfunction "A2_3") (pintype "bidirectional"))
    )
    (net (code "71") (name "UART2_TX_5V") (class "Default")
      (node (ref "U5") (pin "12") (pinfunction "B2_12") (pintype "bidirectional"))
      (node (ref "UART2") (pin "2") (pinfunction "2_2") (pintype "passive"))
    )
    (net (code "72") (name "USB_RX") (class "Default")
      (node (ref "IC1") (pin "15") (pinfunction "TXD_15") (pintype "output"))
      (node (ref "U2") (pin "2") (pinfunction "(RXD0/PCINT8)_PE0_2") (pintype "bidirectional"))
    )
    (net (code "73") (name "USB_TX") (class "Default")
      (node (ref "IC1") (pin "2") (pinfunction "RXD_2") (pintype "input"))
      (node (ref "U2") (pin "3") (pinfunction "(TXD0)_PE1_3") (pintype "bidirectional"))
    )
    (net (code "74") (name "VBUS_SENSE") (class "Default")
      (node (ref "IC1") (pin "12") (pinfunction "CBUS0_12") (pintype "bidirectional"))
      (node (ref "R8") (pin "1") (pinfunction "1_1") (pintype "passive"))
      (node (ref "R9") (pin "2") (pinfunction "2_2") (pintype "passive"))
    )
    (net (code "75") (name "unconnected-(IC1-CBUS3-Pad14)") (class "Default")
      (node (ref "IC1") (pin "14") (pinfunction "CBUS3_14") (pintype "bidirectional"))
    )
    (net (code "76") (name "unconnected-(IC1-~{CTS}-Pad4)") (class "Default")
      (node (ref "IC1") (pin "4") (pinfunction "~{CTS}_4") (pintype "input"))
    )
    (net (code "77") (name "unconnected-(IC1-~{RESET}-Pad9)") (class "Default")
      (node (ref "IC1") (pin "9") (pinfunction "~{RESET}_9") (pintype "input"))
    )
    (net (code "78") (name "unconnected-(IC1-~{RTS}-Pad16)") (class "Default")
      (node (ref "IC1") (pin "16") (pinfunction "~{RTS}_16") (pintype "output"))
    )
    (net (code "79") (name "unconnected-(J3-PadID)") (class "Default")
      (node (ref "J3") (pin "ID") (pinfunction "ID_ID") (pintype "bidirectional"))
    )
    (net (code "80") (name "unconnected-(U1-NC-PadP$6)") (class "Default")
      (node (ref "U1") (pin "P$6") (pinfunction "NC_P$6") (pintype "bidirectional"))
    )
    (net (code "81") (name "unconnected-(U1-NC-PadP$7)") (class "Default")
      (node (ref "U1") (pin "P$7") (pinfunction "NC_P$7") (pintype "bidirectional"))
    )
    (net (code "82") (name "unconnected-(U1-NC-PadP$15)") (class "Default")
      (node (ref "U1") (pin "P$15") (pinfunction "NC_P$15") (pintype "bidirectional"))
    )
    (net (code "83") (name "unconnected-(U1-NC-PadP$16)") (class "Default")
      (node (ref "U1") (pin "P$16") (pinfunction "NC_P$16") (pintype "bidirectional"))
    )
    (net (code "84") (name "unconnected-(U1-NC-PadP$17)") (class "Default")
      (node (ref "U1") (pin "P$17") (pinfunction "NC_P$17") (pintype "bidirectional"))
    )
    (net (code "85") (name "unconnected-(U1-NC-PadP$18)") (class "Default")
      (node (ref "U1") (pin "P$18") (pinfunction "NC_P$18") (pintype "bidirectional"))
    )
    (net (code "86") (name "unconnected-(U1-NC-PadP$20)") (class "Default")
      (node (ref "U1") (pin "P$20") (pinfunction "NC_P$20") (pintype "bidirectional"))
    )
    (net (code "87") (name "unconnected-(U1-RTCM-PadP$14)") (class "Default")
      (node (ref "U1") (pin "P$14") (pinfunction "RTCM_P$14") (pintype "bidirectional"))
    )
    (net (code "88") (name "unconnected-(U1-VBACKUP-PadP$4)") (class "Default")
      (node (ref "U1") (pin "P$4") (pinfunction "VBACKUP_P$4") (pintype "bidirectional"))
    )
    (net (code "89") (name "unconnected-(U2A-(CLKO{slash}ICP3{slash}INT7)_PE7-Pad9)") (class "Default")
      (node (ref "U2") (pin "9") (pinfunction "(CLKO/ICP3/INT7)_PE7_9") (pintype "bidirectional"))
    )
    (net (code "90") (name "unconnected-(U2A-(OC0B)_PG5-Pad1)") (class "Default")
      (node (ref "U2") (pin "1") (pinfunction "(OC0B)_PG5_1") (pintype "bidirectional"))
    )
    (net (code "91") (name "unconnected-(U2A-(OC2A{slash}PCINT4)_PB4-Pad23)") (class "Default")
      (node (ref "U2") (pin "23") (pinfunction "(OC2A/PCINT4)_PB4_23") (pintype "bidirectional"))
    )
    (net (code "92") (name "unconnected-(U2A-(OC2B)_PH6-Pad18)") (class "Default")
      (node (ref "U2") (pin "18") (pinfunction "(OC2B)_PH6_18") (pintype "bidirectional"))
    )
    (net (code "93") (name "unconnected-(U2A-(OC3B{slash}INT4)_PE4-Pad6)") (class "Default")
      (node (ref "U2") (pin "6") (pinfunction "(OC3B/INT4)_PE4_6") (pintype "bidirectional"))
    )
    (net (code "94") (name "unconnected-(U2A-(OC3C{slash}INT5)_PE5-Pad7)") (class "Default")
      (node (ref "U2") (pin "7") (pinfunction "(OC3C/INT5)_PE5_7") (pintype "bidirectional"))
    )
    (net (code "95") (name "unconnected-(U2A-(OC4A)_PH3-Pad15)") (class "Default")
      (node (ref "U2") (pin "15") (pinfunction "(OC4A)_PH3_15") (pintype "bidirectional"))
    )
    (net (code "96") (name "unconnected-(U2A-(OC4B)_PH4-Pad16)") (class "Default")
      (node (ref "U2") (pin "16") (pinfunction "(OC4B)_PH4_16") (pintype "bidirectional"))
    )
    (net (code "97") (name "unconnected-(U2A-(OC4C)_PH5-Pad17)") (class "Default")
      (node (ref "U2") (pin "17") (pinfunction "(OC4C)_PH5_17") (pintype "bidirectional"))
    )
    (net (code "98") (name "unconnected-(U2A-(SS{slash}PCINT0)_PB0-Pad19)") (class "Default")
      (node (ref "U2") (pin "19") (pinfunction "(SS/PCINT0)_PB0_19") (pintype "bidirectional"))
    )
    (net (code "99") (name "unconnected-(U2A-(T0)_PD7-Pad50)") (class "Default")
      (node (ref "U2") (pin "50") (pinfunction "(T0)_PD7_50") (pintype "bidirectional"))
    )
    (net (code "100") (name "unconnected-(U2A-(T1)_PD6-Pad49)") (class "Default")
      (node (ref "U2") (pin "49") (pinfunction "(T1)_PD6_49") (pintype "bidirectional"))
    )
    (net (code "101") (name "unconnected-(U2A-(T3{slash}INT6)_PE6-Pad8)") (class "Default")
      (node (ref "U2") (pin "8") (pinfunction "(T3/INT6)_PE6_8") (pintype "bidirectional"))
    )
    (net (code "102") (name "unconnected-(U2A-(T4)_PH7-Pad27)") (class "Default")
      (node (ref "U2") (pin "27") (pinfunction "(T4)_PH7_27") (pintype "bidirectional"))
    )
    (net (code "103") (name "unconnected-(U2A-(TOSC1)_PG4-Pad29)") (class "Default")
      (node (ref "U2") (pin "29") (pinfunction "(TOSC1)_PG4_29") (pintype "bidirectional"))
    )
    (net (code "104") (name "unconnected-(U2A-(TOSC2)_PG3-Pad28)") (class "Default")
      (node (ref "U2") (pin "28") (pinfunction "(TOSC2)_PG3_28") (pintype "bidirectional"))
    )
    (net (code "105") (name "unconnected-(U2A-(XCK0{slash}AIN0)_PE2-Pad4)") (class "Default")
      (node (ref "U2") (pin "4") (pinfunction "(XCK0/AIN0)_PE2_4") (pintype "bidirectional"))
    )
    (net (code "106") (name "unconnected-(U2A-(XCK2)_PH2-Pad14)") (class "Default")
      (node (ref "U2") (pin "14") (pinfunction "(XCK2)_PH2_14") (pintype "bidirectional"))
    )
    (net (code "107") (name "unconnected-(U2A-PA0_(AD0)-Pad78)") (class "Default")
      (node (ref "U2") (pin "78") (pinfunction "PA0_(AD0)_78") (pintype "bidirectional"))
    )
    (net (code "108") (name "unconnected-(U2A-PA1_(AD1)-Pad77)") (class "Default")
      (node (ref "U2") (pin "77") (pinfunction "PA1_(AD1)_77") (pintype "bidirectional"))
    )
    (net (code "109") (name "unconnected-(U2A-PA2_(AD2)-Pad76)") (class "Default")
      (node (ref "U2") (pin "76") (pinfunction "PA2_(AD2)_76") (pintype "bidirectional"))
    )
    (net (code "110") (name "unconnected-(U2A-PA3_(AD3)-Pad75)") (class "Default")
      (node (ref "U2") (pin "75") (pinfunction "PA3_(AD3)_75") (pintype "bidirectional"))
    )
    (net (code "111") (name "unconnected-(U2A-PA4_(AD4)-Pad74)") (class "Default")
      (node (ref "U2") (pin "74") (pinfunction "PA4_(AD4)_74") (pintype "bidirectional"))
    )
    (net (code "112") (name "unconnected-(U2A-PA5_(AD5)-Pad73)") (class "Default")
      (node (ref "U2") (pin "73") (pinfunction "PA5_(AD5)_73") (pintype "bidirectional"))
    )
    (net (code "113") (name "unconnected-(U2A-PA6_(AD6)-Pad72)") (class "Default")
      (node (ref "U2") (pin "72") (pinfunction "PA6_(AD6)_72") (pintype "bidirectional"))
    )
    (net (code "114") (name "unconnected-(U2A-PA7_(AD7)-Pad71)") (class "Default")
      (node (ref "U2") (pin "71") (pinfunction "PA7_(AD7)_71") (pintype "bidirectional"))
    )
    (net (code "115") (name "unconnected-(U2A-PC0_(A8)-Pad53)") (class "Default")
      (node (ref "U2") (pin "53") (pinfunction "PC0_(A8)_53") (pintype "bidirectional"))
    )
    (net (code "116") (name "unconnected-(U2A-PC1_(A9)-Pad54)") (class "Default")
      (node (ref "U2") (pin "54") (pinfunction "PC1_(A9)_54") (pintype "bidirectional"))
    )
    (net (code "117") (name "unconnected-(U2A-PC2_(A10)-Pad55)") (class "Default")
      (node (ref "U2") (pin "55") (pinfunction "PC2_(A10)_55") (pintype "bidirectional"))
    )
    (net (code "118") (name "unconnected-(U2A-PC3_(A11)-Pad56)") (class "Default")
      (node (ref "U2") (pin "56") (pinfunction "PC3_(A11)_56") (pintype "bidirectional"))
    )
    (net (code "119") (name "unconnected-(U2A-PC4_(A12)-Pad57)") (class "Default")
      (node (ref "U2") (pin "57") (pinfunction "PC4_(A12)_57") (pintype "bidirectional"))
    )
    (net (code "120") (name "unconnected-(U2A-PC5_(A13)-Pad58)") (class "Default")
      (node (ref "U2") (pin "58") (pinfunction "PC5_(A13)_58") (pintype "bidirectional"))
    )
    (net (code "121") (name "unconnected-(U2A-PC6_(A14)-Pad59)") (class "Default")
      (node (ref "U2") (pin "59") (pinfunction "PC6_(A14)_59") (pintype "bidirectional"))
    )
    (net (code "122") (name "unconnected-(U2A-PC7_(A15)-Pad60)") (class "Default")
      (node (ref "U2") (pin "60") (pinfunction "PC7_(A15)_60") (pintype "bidirectional"))
    )
    (net (code "123") (name "unconnected-(U2A-PF0_(ADC0)-Pad97)") (class "Default")
      (node (ref "U2") (pin "97") (pinfunction "PF0_(ADC0)_97") (pintype "bidirectional"))
    )
    (net (code "124") (name "unconnected-(U2A-PF1_(ADC1)-Pad96)") (class "Default")
      (node (ref "U2") (pin "96") (pinfunction "PF1_(ADC1)_96") (pintype "bidirectional"))
    )
    (net (code "125") (name "unconnected-(U2A-PF2_(ADC2)-Pad95)") (class "Default")
      (node (ref "U2") (pin "95") (pinfunction "PF2_(ADC2)_95") (pintype "bidirectional"))
    )
    (net (code "126") (name "unconnected-(U2A-PF3_(ADC3)-Pad94)") (class "Default")
      (node (ref "U2") (pin "94") (pinfunction "PF3_(ADC3)_94") (pintype "bidirectional"))
    )
    (net (code "127") (name "unconnected-(U2A-PF4_(ADC4{slash}TCK)-Pad93)") (class "Default")
      (node (ref "U2") (pin "93") (pinfunction "PF4_(ADC4/TCK)_93") (pintype "bidirectional"))
    )
    (net (code "128") (name "unconnected-(U2A-PF5_(ADC5{slash}TMS)-Pad92)") (class "Default")
      (node (ref "U2") (pin "92") (pinfunction "PF5_(ADC5/TMS)_92") (pintype "bidirectional"))
    )
    (net (code "129") (name "unconnected-(U2A-PF6_(ADC6{slash}TDO)-Pad91)") (class "Default")
      (node (ref "U2") (pin "91") (pinfunction "PF6_(ADC6/TDO)_91") (pintype "bidirectional"))
    )
    (net (code "130") (name "unconnected-(U2A-PF7_(ADC7{slash}TDI)-Pad90)") (class "Default")
      (node (ref "U2") (pin "90") (pinfunction "PF7_(ADC7/TDI)_90") (pintype "bidirectional"))
    )
    (net (code "131") (name "unconnected-(U2A-PG0_(~{WR})-Pad51)") (class "Default")
      (node (ref "U2") (pin "51") (pinfunction "PG0_(~{WR})_51") (pintype "bidirectional"))
    )
    (net (code "132") (name "unconnected-(U2A-PG1_(~{RD})-Pad52)") (class "Default")
      (node (ref "U2") (pin "52") (pinfunction "PG1_(~{RD})_52") (pintype "bidirectional"))
    )
    (net (code "133") (name "unconnected-(U2A-PG2_(ALE)-Pad70)") (class "Default")
      (node (ref "U2") (pin "70") (pinfunction "PG2_(ALE)_70") (pintype "bidirectional"))
    )
    (net (code "134") (name "unconnected-(U2A-PK6_(ADC14{slash}PCINT22)-Pad83)") (class "Default")
      (node (ref "U2") (pin "83") (pinfunction "PK6_(ADC14/PCINT22)_83") (pintype "bidirectional"))
    )
    (net (code "135") (name "unconnected-(U2A-PK7_(ADC15{slash}PCINT23)-Pad82)") (class "Default")
      (node (ref "U2") (pin "82") (pinfunction "PK7_(ADC15/PCINT23)_82") (pintype "bidirectional"))
    )
    (net (code "136") (name "~{GPS_RST}") (class "Default")
      (node (ref "R1") (pin "1") (pinfunction "1_1") (pintype "passive"))
      (node (ref "U1") (pin "P$2") (pinfunction "NRESET_P$2") (pintype "bidirectional"))
      (node (ref "U2") (pin "47") (pinfunction "(ICP1)_PD4_47") (pintype "bidirectional"))
    )
    (net (code "137") (name "~{LORA_RST}") (class "Default")
      (node (ref "R21") (pin "1") (pinfunction "1_1") (pintype "passive"))
      (node (ref "U2") (pin "69") (pinfunction "PJ6_(PCINT15)_69") (pintype "bidirectional"))
      (node (ref "U4") (pin "6") (pinfunction "RESET_6") (pintype "input"))
    )
    (net (code "138") (name "~{LORA_SS}") (class "Default")
      (node (ref "U2") (pin "79") (pinfunction "PJ7_79") (pintype "bidirectional"))
      (node (ref "U4") (pin "5") (pinfunction "NSS_5") (pintype "input"))
    )
    (net (code "139") (name "~{RESET}") (class "Default")
      (node (ref "ISP") (pin "5") (pinfunction "5_5") (pintype "passive"))
      (node (ref "R13") (pin "1") (pinfunction "1_1") (pintype "passive"))
      (node (ref "R3") (pin "1") (pinfunction "1_1") (pintype "passive"))
      (node (ref "RESET") (pin "1") (pinfunction "A0_1") (pintype "bidirectional"))
      (node (ref "RESET") (pin "2") (pinfunction "A1_2") (pintype "bidirectional"))
      (node (ref "U2") (pin "30") (pinfunction "~{RESET}_30") (pintype "input"))
    )
  )
)
